# Schematic_L1.net
KiCad netlist of a schematic drawn in Altium Designer
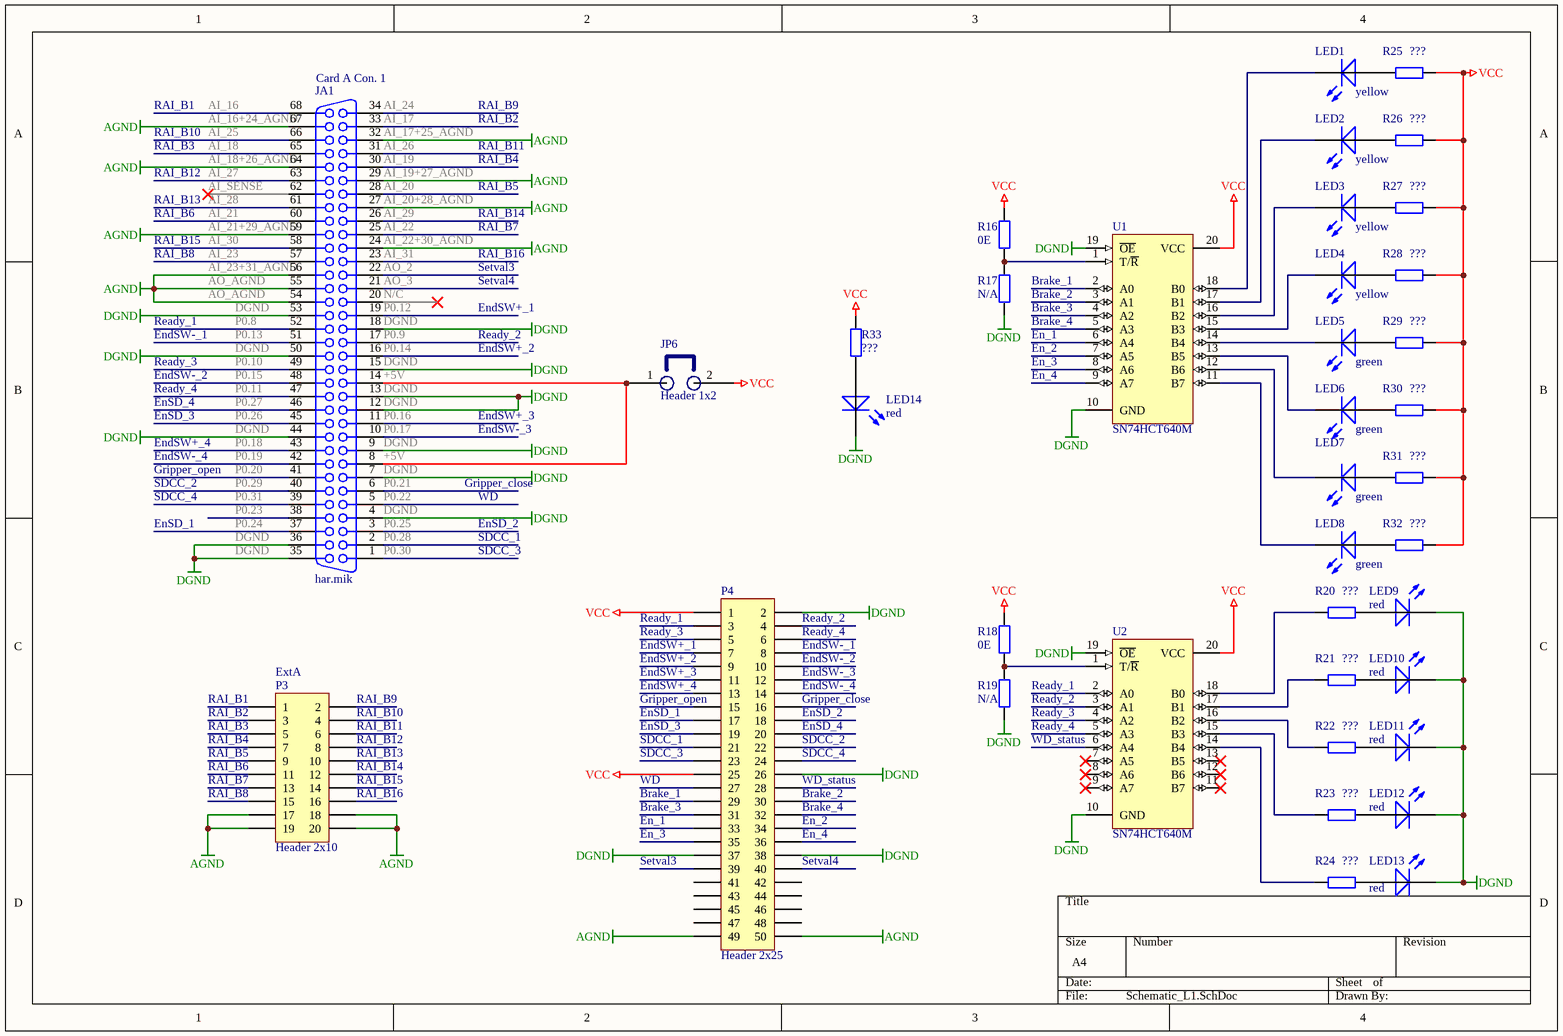
[diagram p0: Schematic_L1.SchDoc]

(export (version "E")
  (design (tool "Eeschema 10.0.6"))
  (components
    (comp (ref "JA1")
      (value "har.mik")
      (footprint "HAR-MIK P/S 68 SA")
      (description "TB 60 01 068 5232")
      (fields (field (name "PUBLISHER") "Altium Limited"))
      (libsource (lib "Integrated_Library") (part "Connector 68"))
    )
    (comp (ref "JP6")
      (value "Header 1x2")
      (footprint "Header - 1x2 - V")
      (libsource (lib "Integrated_Library") (part "Jumper"))
    )
    (comp (ref "LED1")
      (value "yellow")
      (footprint "KM2520")
      (description "Typical LED")
      (libsource (lib "mzueger") (part "LED"))
    )
    (comp (ref "LED2")
      (value "yellow")
      (footprint "KM2520")
      (description "Typical LED")
      (libsource (lib "mzueger") (part "LED"))
    )
    (comp (ref "LED3")
      (value "yellow")
      (footprint "KM2520")
      (description "Typical LED")
      (libsource (lib "mzueger") (part "LED"))
    )
    (comp (ref "LED4")
      (value "yellow")
      (footprint "KM2520")
      (description "Typical LED")
      (libsource (lib "mzueger") (part "LED"))
    )
    (comp (ref "LED5")
      (value "green")
      (footprint "KM2520")
      (description "Typical LED")
      (libsource (lib "mzueger") (part "LED"))
    )
    (comp (ref "LED6")
      (value "green")
      (footprint "KM2520")
      (description "Typical LED")
      (libsource (lib "mzueger") (part "LED"))
    )
    (comp (ref "LED7")
      (value "green")
      (footprint "KM2520")
      (description "Typical LED")
      (libsource (lib "mzueger") (part "LED"))
    )
    (comp (ref "LED8")
      (value "green")
      (footprint "KM2520")
      (description "Typical LED")
      (libsource (lib "mzueger") (part "LED"))
    )
    (comp (ref "LED9")
      (value "red")
      (footprint "KM2520")
      (description "Typical LED")
      (libsource (lib "mzueger") (part "LED"))
    )
    (comp (ref "LED10")
      (value "red")
      (footprint "KM2520")
      (description "Typical LED")
      (libsource (lib "mzueger") (part "LED"))
    )
    (comp (ref "LED11")
      (value "red")
      (footprint "KM2520")
      (description "Typical LED")
      (libsource (lib "mzueger") (part "LED"))
    )
    (comp (ref "LED12")
      (value "red")
      (footprint "KM2520")
      (description "Typical LED")
      (libsource (lib "mzueger") (part "LED"))
    )
    (comp (ref "LED13")
      (value "red")
      (footprint "KM2520")
      (description "Typical LED")
      (libsource (lib "mzueger") (part "LED"))
    )
    (comp (ref "LED14")
      (value "red")
      (footprint "KM2520")
      (description "Typical LED")
      (libsource (lib "mzueger") (part "LED"))
    )
    (comp (ref "P3")
      (value "Header 2x10")
      (footprint "Header - 2x10 - V")
      (description "Header, 10-Pin, Dual row")
      (fields (field (name "PUBLISHER") "Altium Limited"))
      (libsource (lib "mzueger") (part "Header 2x10"))
    )
    (comp (ref "P4")
      (value "Header 2x25")
      (footprint "Header - 2x25 - V")
      (description "Header, 25-Pin, Dual row")
      (fields (field (name "PUBLISHER") "Altium Limited"))
      (libsource (lib "mzueger") (part "Header 2x25"))
    )
    (comp (ref "R16")
      (value "0E")
      (footprint "0805")
      (description "Resistor")
      (fields (field (name "#PUBLISHER") "Dr. A. Heinzelmann"))
      (libsource (lib "") (part "R_1"))
    )
    (comp (ref "R17")
      (value "N/A")
      (footprint "0805")
      (description "Resistor")
      (fields (field (name "#PUBLISHER") "Dr. A. Heinzelmann"))
      (libsource (lib "") (part "R_1"))
    )
    (comp (ref "R18")
      (value "0E")
      (footprint "0805")
      (description "Resistor")
      (fields (field (name "#PUBLISHER") "Dr. A. Heinzelmann"))
      (libsource (lib "") (part "R_1"))
    )
    (comp (ref "R19")
      (value "N/A")
      (footprint "0805")
      (description "Resistor")
      (fields (field (name "#PUBLISHER") "Dr. A. Heinzelmann"))
      (libsource (lib "") (part "R_1"))
    )
    (comp (ref "R20")
      (value "???")
      (footprint "0805")
      (description "Resistor")
      (fields (field (name "#PUBLISHER") "Dr. A. Heinzelmann"))
      (libsource (lib "mzueger") (part "R"))
    )
    (comp (ref "R21")
      (value "???")
      (footprint "0805")
      (description "Resistor")
      (fields (field (name "#PUBLISHER") "Dr. A. Heinzelmann"))
      (libsource (lib "mzueger") (part "R"))
    )
    (comp (ref "R22")
      (value "???")
      (footprint "0805")
      (description "Resistor")
      (fields (field (name "#PUBLISHER") "Dr. A. Heinzelmann"))
      (libsource (lib "mzueger") (part "R"))
    )
    (comp (ref "R23")
      (value "???")
      (footprint "0805")
      (description "Resistor")
      (fields (field (name "#PUBLISHER") "Dr. A. Heinzelmann"))
      (libsource (lib "mzueger") (part "R"))
    )
    (comp (ref "R24")
      (value "???")
      (footprint "0805")
      (description "Resistor")
      (fields (field (name "#PUBLISHER") "Dr. A. Heinzelmann"))
      (libsource (lib "mzueger") (part "R"))
    )
    (comp (ref "R25")
      (value "???")
      (footprint "0805")
      (description "Resistor")
      (fields (field (name "#PUBLISHER") "Dr. A. Heinzelmann"))
      (libsource (lib "mzueger") (part "R"))
    )
    (comp (ref "R26")
      (value "???")
      (footprint "0805")
      (description "Resistor")
      (fields (field (name "#PUBLISHER") "Dr. A. Heinzelmann"))
      (libsource (lib "mzueger") (part "R"))
    )
    (comp (ref "R27")
      (value "???")
      (footprint "0805")
      (description "Resistor")
      (fields (field (name "#PUBLISHER") "Dr. A. Heinzelmann"))
      (libsource (lib "mzueger") (part "R"))
    )
    (comp (ref "R28")
      (value "???")
      (footprint "0805")
      (description "Resistor")
      (fields (field (name "#PUBLISHER") "Dr. A. Heinzelmann"))
      (libsource (lib "mzueger") (part "R"))
    )
    (comp (ref "R29")
      (value "???")
      (footprint "0805")
      (description "Resistor")
      (fields (field (name "#PUBLISHER") "Dr. A. Heinzelmann"))
      (libsource (lib "mzueger") (part "R"))
    )
    (comp (ref "R30")
      (value "???")
      (footprint "0805")
      (description "Resistor")
      (fields (field (name "#PUBLISHER") "Dr. A. Heinzelmann"))
      (libsource (lib "mzueger") (part "R"))
    )
    (comp (ref "R31")
      (value "???")
      (footprint "0805")
      (description "Resistor")
      (fields (field (name "#PUBLISHER") "Dr. A. Heinzelmann"))
      (libsource (lib "mzueger") (part "R"))
    )
    (comp (ref "R32")
      (value "???")
      (footprint "0805")
      (description "Resistor")
      (fields (field (name "#PUBLISHER") "Dr. A. Heinzelmann"))
      (libsource (lib "mzueger") (part "R"))
    )
    (comp (ref "R33")
      (value "???")
      (footprint "0805")
      (description "Resistor")
      (fields (field (name "#PUBLISHER") "Dr. A. Heinzelmann"))
      (libsource (lib "") (part "R_1"))
    )
    (comp (ref "U1")
      (value "SN74HCT640M")
      (footprint "DW020_N")
      (description "Octal Bus Transceiver with 3-State Outputs")
      (fields (field (name "PUBLISHER") "Altium Limited"))
      (libsource (lib "TI Interface 8-Bit Line Transceiver") (part "SN74HCT640DW"))
    )
    (comp (ref "U2")
      (value "SN74HCT640M")
      (footprint "DW020_N")
      (description "Octal Bus Transceiver with 3-State Outputs")
      (fields (field (name "PUBLISHER") "Altium Limited"))
      (libsource (lib "TI Interface 8-Bit Line Transceiver") (part "SN74HCT640DW"))
    )
  )
  (nets
    (net (code "1") (name "/Brake_1") (class "Default")
      (node (ref "P4") (pin "29") (pinfunction "29_29") (pintype "passive"))
      (node (ref "U1") (pin "2") (pinfunction "A0_2") (pintype "bidirectional"))
    )
    (net (code "2") (name "/Brake_2") (class "Default")
      (node (ref "P4") (pin "30") (pinfunction "30_30") (pintype "passive"))
      (node (ref "U1") (pin "3") (pinfunction "A1_3") (pintype "bidirectional"))
    )
    (net (code "3") (name "/Brake_3") (class "Default")
      (node (ref "P4") (pin "31") (pinfunction "31_31") (pintype "passive"))
      (node (ref "U1") (pin "4") (pinfunction "A2_4") (pintype "bidirectional"))
    )
    (net (code "4") (name "/Brake_4") (class "Default")
      (node (ref "P4") (pin "32") (pinfunction "32_32") (pintype "passive"))
      (node (ref "U1") (pin "5") (pinfunction "A3_5") (pintype "bidirectional"))
    )
    (net (code "5") (name "/EnSD_1") (class "Default")
      (node (ref "JA1") (pin "37") (pinfunction "37_37") (pintype "passive"))
      (node (ref "P4") (pin "17") (pinfunction "17_17") (pintype "passive"))
    )
    (net (code "6") (name "/EnSD_2") (class "Default")
      (node (ref "JA1") (pin "3") (pinfunction "3_3") (pintype "passive"))
      (node (ref "P4") (pin "18") (pinfunction "18_18") (pintype "passive"))
    )
    (net (code "7") (name "/EnSD_3") (class "Default")
      (node (ref "JA1") (pin "45") (pinfunction "45_45") (pintype "passive"))
      (node (ref "P4") (pin "19") (pinfunction "19_19") (pintype "passive"))
    )
    (net (code "8") (name "/EnSD_4") (class "Default")
      (node (ref "JA1") (pin "46") (pinfunction "46_46") (pintype "passive"))
      (node (ref "P4") (pin "20") (pinfunction "20_20") (pintype "passive"))
    )
    (net (code "9") (name "/En_1") (class "Default")
      (node (ref "P4") (pin "33") (pinfunction "33_33") (pintype "passive"))
      (node (ref "U1") (pin "6") (pinfunction "A4_6") (pintype "bidirectional"))
    )
    (net (code "10") (name "/En_2") (class "Default")
      (node (ref "P4") (pin "34") (pinfunction "34_34") (pintype "passive"))
      (node (ref "U1") (pin "7") (pinfunction "A5_7") (pintype "bidirectional"))
    )
    (net (code "11") (name "/En_3") (class "Default")
      (node (ref "P4") (pin "35") (pinfunction "35_35") (pintype "passive"))
      (node (ref "U1") (pin "8") (pinfunction "A6_8") (pintype "bidirectional"))
    )
    (net (code "12") (name "/En_4") (class "Default")
      (node (ref "P4") (pin "36") (pinfunction "36_36") (pintype "passive"))
      (node (ref "U1") (pin "9") (pinfunction "A7_9") (pintype "bidirectional"))
    )
    (net (code "13") (name "/EndSW+_1") (class "Default")
      (node (ref "JA1") (pin "19") (pinfunction "19_19") (pintype "passive"))
      (node (ref "P4") (pin "7") (pinfunction "7_7") (pintype "passive"))
    )
    (net (code "14") (name "/EndSW+_2") (class "Default")
      (node (ref "JA1") (pin "16") (pinfunction "16_16") (pintype "passive"))
      (node (ref "P4") (pin "9") (pinfunction "9_9") (pintype "passive"))
    )
    (net (code "15") (name "/EndSW+_3") (class "Default")
      (node (ref "JA1") (pin "11") (pinfunction "11_11") (pintype "passive"))
      (node (ref "P4") (pin "11") (pinfunction "11_11") (pintype "passive"))
    )
    (net (code "16") (name "/EndSW+_4") (class "Default")
      (node (ref "JA1") (pin "43") (pinfunction "43_43") (pintype "passive"))
      (node (ref "P4") (pin "13") (pinfunction "13_13") (pintype "passive"))
    )
    (net (code "17") (name "/EndSW-_1") (class "Default")
      (node (ref "JA1") (pin "51") (pinfunction "51_51") (pintype "passive"))
      (node (ref "P4") (pin "8") (pinfunction "8_8") (pintype "passive"))
    )
    (net (code "18") (name "/EndSW-_2") (class "Default")
      (node (ref "JA1") (pin "48") (pinfunction "48_48") (pintype "passive"))
      (node (ref "P4") (pin "10") (pinfunction "10_10") (pintype "passive"))
    )
    (net (code "19") (name "/EndSW-_3") (class "Default")
      (node (ref "JA1") (pin "10") (pinfunction "10_10") (pintype "passive"))
      (node (ref "P4") (pin "12") (pinfunction "12_12") (pintype "passive"))
    )
    (net (code "20") (name "/EndSW-_4") (class "Default")
      (node (ref "JA1") (pin "42") (pinfunction "42_42") (pintype "passive"))
      (node (ref "P4") (pin "14") (pinfunction "14_14") (pintype "passive"))
    )
    (net (code "21") (name "/Gripper_close") (class "Default")
      (node (ref "JA1") (pin "6") (pinfunction "6_6") (pintype "passive"))
      (node (ref "P4") (pin "16") (pinfunction "16_16") (pintype "passive"))
    )
    (net (code "22") (name "/Gripper_open") (class "Default")
      (node (ref "JA1") (pin "41") (pinfunction "41_41") (pintype "passive"))
      (node (ref "P4") (pin "15") (pinfunction "15_15") (pintype "passive"))
    )
    (net (code "23") (name "/RAI_B1") (class "Default")
      (node (ref "JA1") (pin "68") (pinfunction "68_68") (pintype "passive"))
      (node (ref "P3") (pin "1") (pinfunction "1_1") (pintype "passive"))
    )
    (net (code "24") (name "/RAI_B2") (class "Default")
      (node (ref "JA1") (pin "33") (pinfunction "33_33") (pintype "passive"))
      (node (ref "P3") (pin "3") (pinfunction "3_3") (pintype "passive"))
    )
    (net (code "25") (name "/RAI_B3") (class "Default")
      (node (ref "JA1") (pin "65") (pinfunction "65_65") (pintype "passive"))
      (node (ref "P3") (pin "5") (pinfunction "5_5") (pintype "passive"))
    )
    (net (code "26") (name "/RAI_B4") (class "Default")
      (node (ref "JA1") (pin "30") (pinfunction "30_30") (pintype "passive"))
      (node (ref "P3") (pin "7") (pinfunction "7_7") (pintype "passive"))
    )
    (net (code "27") (name "/RAI_B5") (class "Default")
      (node (ref "JA1") (pin "28") (pinfunction "28_28") (pintype "passive"))
      (node (ref "P3") (pin "9") (pinfunction "9_9") (pintype "passive"))
    )
    (net (code "28") (name "/RAI_B6") (class "Default")
      (node (ref "JA1") (pin "60") (pinfunction "60_60") (pintype "passive"))
      (node (ref "P3") (pin "11") (pinfunction "11_11") (pintype "passive"))
    )
    (net (code "29") (name "/RAI_B7") (class "Default")
      (node (ref "JA1") (pin "25") (pinfunction "25_25") (pintype "passive"))
      (node (ref "P3") (pin "13") (pinfunction "13_13") (pintype "passive"))
    )
    (net (code "30") (name "/RAI_B8") (class "Default")
      (node (ref "JA1") (pin "57") (pinfunction "57_57") (pintype "passive"))
      (node (ref "P3") (pin "15") (pinfunction "15_15") (pintype "passive"))
    )
    (net (code "31") (name "/RAI_B9") (class "Default")
      (node (ref "JA1") (pin "34") (pinfunction "34_34") (pintype "passive"))
      (node (ref "P3") (pin "2") (pinfunction "2_2") (pintype "passive"))
    )
    (net (code "32") (name "/RAI_B10") (class "Default")
      (node (ref "JA1") (pin "66") (pinfunction "66_66") (pintype "passive"))
      (node (ref "P3") (pin "4") (pinfunction "4_4") (pintype "passive"))
    )
    (net (code "33") (name "/RAI_B11") (class "Default")
      (node (ref "JA1") (pin "31") (pinfunction "31_31") (pintype "passive"))
      (node (ref "P3") (pin "6") (pinfunction "6_6") (pintype "passive"))
    )
    (net (code "34") (name "/RAI_B12") (class "Default")
      (node (ref "JA1") (pin "63") (pinfunction "63_63") (pintype "passive"))
      (node (ref "P3") (pin "8") (pinfunction "8_8") (pintype "passive"))
    )
    (net (code "35") (name "/RAI_B13") (class "Default")
      (node (ref "JA1") (pin "61") (pinfunction "61_61") (pintype "passive"))
      (node (ref "P3") (pin "10") (pinfunction "10_10") (pintype "passive"))
    )
    (net (code "36") (name "/RAI_B14") (class "Default")
      (node (ref "JA1") (pin "26") (pinfunction "26_26") (pintype "passive"))
      (node (ref "P3") (pin "12") (pinfunction "12_12") (pintype "passive"))
    )
    (net (code "37") (name "/RAI_B15") (class "Default")
      (node (ref "JA1") (pin "58") (pinfunction "58_58") (pintype "passive"))
      (node (ref "P3") (pin "14") (pinfunction "14_14") (pintype "passive"))
    )
    (net (code "38") (name "/RAI_B16") (class "Default")
      (node (ref "JA1") (pin "23") (pinfunction "23_23") (pintype "passive"))
      (node (ref "P3") (pin "16") (pinfunction "16_16") (pintype "passive"))
    )
    (net (code "39") (name "/Ready_1") (class "Default")
      (node (ref "JA1") (pin "52") (pinfunction "52_52") (pintype "passive"))
      (node (ref "P4") (pin "3") (pinfunction "3_3") (pintype "passive"))
      (node (ref "U2") (pin "2") (pinfunction "A0_2") (pintype "bidirectional"))
    )
    (net (code "40") (name "/Ready_2") (class "Default")
      (node (ref "JA1") (pin "17") (pinfunction "17_17") (pintype "passive"))
      (node (ref "P4") (pin "4") (pinfunction "4_4") (pintype "passive"))
      (node (ref "U2") (pin "3") (pinfunction "A1_3") (pintype "bidirectional"))
    )
    (net (code "41") (name "/Ready_3") (class "Default")
      (node (ref "JA1") (pin "49") (pinfunction "49_49") (pintype "passive"))
      (node (ref "P4") (pin "5") (pinfunction "5_5") (pintype "passive"))
      (node (ref "U2") (pin "4") (pinfunction "A2_4") (pintype "bidirectional"))
    )
    (net (code "42") (name "/Ready_4") (class "Default")
      (node (ref "JA1") (pin "47") (pinfunction "47_47") (pintype "passive"))
      (node (ref "P4") (pin "6") (pinfunction "6_6") (pintype "passive"))
      (node (ref "U2") (pin "5") (pinfunction "A3_5") (pintype "bidirectional"))
    )
    (net (code "43") (name "/SDCC_1") (class "Default")
      (node (ref "JA1") (pin "2") (pinfunction "2_2") (pintype "passive"))
      (node (ref "P4") (pin "21") (pinfunction "21_21") (pintype "passive"))
    )
    (net (code "44") (name "/SDCC_2") (class "Default")
      (node (ref "JA1") (pin "40") (pinfunction "40_40") (pintype "passive"))
      (node (ref "P4") (pin "22") (pinfunction "22_22") (pintype "passive"))
    )
    (net (code "45") (name "/SDCC_3") (class "Default")
      (node (ref "JA1") (pin "1") (pinfunction "1_1") (pintype "passive"))
      (node (ref "P4") (pin "23") (pinfunction "23_23") (pintype "passive"))
    )
    (net (code "46") (name "/SDCC_4") (class "Default")
      (node (ref "JA1") (pin "39") (pinfunction "39_39") (pintype "passive"))
      (node (ref "P4") (pin "24") (pinfunction "24_24") (pintype "passive"))
    )
    (net (code "47") (name "/Setval3") (class "Default")
      (node (ref "JA1") (pin "22") (pinfunction "22_22") (pintype "passive"))
      (node (ref "P4") (pin "39") (pinfunction "39_39") (pintype "passive"))
    )
    (net (code "48") (name "/Setval4") (class "Default")
      (node (ref "JA1") (pin "21") (pinfunction "21_21") (pintype "passive"))
      (node (ref "P4") (pin "40") (pinfunction "40_40") (pintype "passive"))
    )
    (net (code "49") (name "/WD") (class "Default")
      (node (ref "JA1") (pin "5") (pinfunction "5_5") (pintype "passive"))
      (node (ref "P4") (pin "27") (pinfunction "27_27") (pintype "passive"))
    )
    (net (code "50") (name "/WD_status") (class "Default")
      (node (ref "P4") (pin "28") (pinfunction "28_28") (pintype "passive"))
      (node (ref "U2") (pin "6") (pinfunction "A4_6") (pintype "bidirectional"))
    )
    (net (code "51") (name "AGND") (class "Default")
      (node (ref "JA1") (pin "24") (pinfunction "24_24") (pintype "passive"))
      (node (ref "JA1") (pin "27") (pinfunction "27_27") (pintype "passive"))
      (node (ref "JA1") (pin "29") (pinfunction "29_29") (pintype "passive"))
      (node (ref "JA1") (pin "32") (pinfunction "32_32") (pintype "passive"))
      (node (ref "JA1") (pin "54") (pinfunction "54_54") (pintype "passive"))
      (node (ref "JA1") (pin "55") (pinfunction "55_55") (pintype "passive"))
      (node (ref "JA1") (pin "56") (pinfunction "56_56") (pintype "passive"))
      (node (ref "JA1") (pin "59") (pinfunction "59_59") (pintype "passive"))
      (node (ref "JA1") (pin "64") (pinfunction "64_64") (pintype "passive"))
      (node (ref "JA1") (pin "67") (pinfunction "67_67") (pintype "passive"))
      (node (ref "P3") (pin "17") (pinfunction "17_17") (pintype "passive"))
      (node (ref "P3") (pin "18") (pinfunction "18_18") (pintype "passive"))
      (node (ref "P3") (pin "19") (pinfunction "19_19") (pintype "passive"))
      (node (ref "P3") (pin "20") (pinfunction "20_20") (pintype "passive"))
      (node (ref "P4") (pin "49") (pinfunction "49_49") (pintype "passive"))
      (node (ref "P4") (pin "50") (pinfunction "50_50") (pintype "passive"))
    )
    (net (code "52") (name "DGND") (class "Default")
      (node (ref "JA1") (pin "12") (pinfunction "12_12") (pintype "passive"))
      (node (ref "JA1") (pin "13") (pinfunction "13_13") (pintype "passive"))
      (node (ref "JA1") (pin "15") (pinfunction "15_15") (pintype "passive"))
      (node (ref "JA1") (pin "18") (pinfunction "18_18") (pintype "passive"))
      (node (ref "JA1") (pin "35") (pinfunction "35_35") (pintype "passive"))
      (node (ref "JA1") (pin "36") (pinfunction "36_36") (pintype "passive"))
      (node (ref "JA1") (pin "4") (pinfunction "4_4") (pintype "passive"))
      (node (ref "JA1") (pin "44") (pinfunction "44_44") (pintype "passive"))
      (node (ref "JA1") (pin "50") (pinfunction "50_50") (pintype "passive"))
      (node (ref "JA1") (pin "53") (pinfunction "53_53") (pintype "passive"))
      (node (ref "JA1") (pin "7") (pinfunction "7_7") (pintype "passive"))
      (node (ref "JA1") (pin "9") (pinfunction "9_9") (pintype "passive"))
      (node (ref "LED10") (pin "1") (pinfunction "K_1") (pintype "passive"))
      (node (ref "LED11") (pin "1") (pinfunction "K_1") (pintype "passive"))
      (node (ref "LED12") (pin "1") (pinfunction "K_1") (pintype "passive"))
      (node (ref "LED13") (pin "1") (pinfunction "K_1") (pintype "passive"))
      (node (ref "LED14") (pin "1") (pinfunction "K_1") (pintype "passive"))
      (node (ref "LED9") (pin "1") (pinfunction "K_1") (pintype "passive"))
      (node (ref "P4") (pin "2") (pinfunction "2_2") (pintype "passive"))
      (node (ref "P4") (pin "26") (pinfunction "26_26") (pintype "passive"))
      (node (ref "P4") (pin "37") (pinfunction "37_37") (pintype "passive"))
      (node (ref "P4") (pin "38") (pinfunction "38_38") (pintype "passive"))
      (node (ref "R17") (pin "1") (pinfunction "1_1") (pintype "passive"))
      (node (ref "R19") (pin "1") (pinfunction "1_1") (pintype "passive"))
      (node (ref "U1") (pin "10") (pinfunction "GND_10") (pintype "power_in"))
      (node (ref "U1") (pin "19") (pinfunction "~{OE}_19") (pintype "input"))
      (node (ref "U2") (pin "10") (pinfunction "GND_10") (pintype "power_in"))
      (node (ref "U2") (pin "19") (pinfunction "~{OE}_19") (pintype "input"))
    )
    (net (code "53") (name "Net-(JA1-Pad14)") (class "Default")
      (node (ref "JA1") (pin "14") (pinfunction "14_14") (pintype "passive"))
      (node (ref "JA1") (pin "8") (pinfunction "8_8") (pintype "passive"))
      (node (ref "JP6") (pin "1") (pinfunction "1_1") (pintype "passive"))
    )
    (net (code "54") (name "Net-(LED1-A)") (class "Default")
      (node (ref "LED1") (pin "2") (pinfunction "A_2") (pintype "passive"))
      (node (ref "R25") (pin "1") (pinfunction "1_1") (pintype "passive"))
    )
    (net (code "55") (name "Net-(LED1-K)") (class "Default")
      (node (ref "LED1") (pin "1") (pinfunction "K_1") (pintype "passive"))
      (node (ref "U1") (pin "18") (pinfunction "B0_18") (pintype "bidirectional"))
    )
    (net (code "56") (name "Net-(LED2-A)") (class "Default")
      (node (ref "LED2") (pin "2") (pinfunction "A_2") (pintype "passive"))
      (node (ref "R26") (pin "1") (pinfunction "1_1") (pintype "passive"))
    )
    (net (code "57") (name "Net-(LED2-K)") (class "Default")
      (node (ref "LED2") (pin "1") (pinfunction "K_1") (pintype "passive"))
      (node (ref "U1") (pin "17") (pinfunction "B1_17") (pintype "bidirectional"))
    )
    (net (code "58") (name "Net-(LED3-A)") (class "Default")
      (node (ref "LED3") (pin "2") (pinfunction "A_2") (pintype "passive"))
      (node (ref "R27") (pin "1") (pinfunction "1_1") (pintype "passive"))
    )
    (net (code "59") (name "Net-(LED3-K)") (class "Default")
      (node (ref "LED3") (pin "1") (pinfunction "K_1") (pintype "passive"))
      (node (ref "U1") (pin "16") (pinfunction "B2_16") (pintype "bidirectional"))
    )
    (net (code "60") (name "Net-(LED4-A)") (class "Default")
      (node (ref "LED4") (pin "2") (pinfunction "A_2") (pintype "passive"))
      (node (ref "R28") (pin "1") (pinfunction "1_1") (pintype "passive"))
    )
    (net (code "61") (name "Net-(LED4-K)") (class "Default")
      (node (ref "LED4") (pin "1") (pinfunction "K_1") (pintype "passive"))
      (node (ref "U1") (pin "15") (pinfunction "B3_15") (pintype "bidirectional"))
    )
    (net (code "62") (name "Net-(LED5-A)") (class "Default")
      (node (ref "LED5") (pin "2") (pinfunction "A_2") (pintype "passive"))
      (node (ref "R29") (pin "1") (pinfunction "1_1") (pintype "passive"))
    )
    (net (code "63") (name "Net-(LED5-K)") (class "Default")
      (node (ref "LED5") (pin "1") (pinfunction "K_1") (pintype "passive"))
      (node (ref "U1") (pin "14") (pinfunction "B4_14") (pintype "bidirectional"))
    )
    (net (code "64") (name "Net-(LED6-A)") (class "Default")
      (node (ref "LED6") (pin "2") (pinfunction "A_2") (pintype "passive"))
      (node (ref "R30") (pin "1") (pinfunction "1_1") (pintype "passive"))
    )
    (net (code "65") (name "Net-(LED6-K)") (class "Default")
      (node (ref "LED6") (pin "1") (pinfunction "K_1") (pintype "passive"))
      (node (ref "U1") (pin "13") (pinfunction "B5_13") (pintype "bidirectional"))
    )
    (net (code "66") (name "Net-(LED7-A)") (class "Default")
      (node (ref "LED7") (pin "2") (pinfunction "A_2") (pintype "passive"))
      (node (ref "R31") (pin "1") (pinfunction "1_1") (pintype "passive"))
    )
    (net (code "67") (name "Net-(LED7-K)") (class "Default")
      (node (ref "LED7") (pin "1") (pinfunction "K_1") (pintype "passive"))
      (node (ref "U1") (pin "12") (pinfunction "B6_12") (pintype "bidirectional"))
    )
    (net (code "68") (name "Net-(LED8-A)") (class "Default")
      (node (ref "LED8") (pin "2") (pinfunction "A_2") (pintype "passive"))
      (node (ref "R32") (pin "1") (pinfunction "1_1") (pintype "passive"))
    )
    (net (code "69") (name "Net-(LED8-K)") (class "Default")
      (node (ref "LED8") (pin "1") (pinfunction "K_1") (pintype "passive"))
      (node (ref "U1") (pin "11") (pinfunction "B7_11") (pintype "bidirectional"))
    )
    (net (code "70") (name "Net-(LED9-A)") (class "Default")
      (node (ref "LED9") (pin "2") (pinfunction "A_2") (pintype "passive"))
      (node (ref "R20") (pin "2") (pinfunction "2_2") (pintype "passive"))
    )
    (net (code "71") (name "Net-(LED10-A)") (class "Default")
      (node (ref "LED10") (pin "2") (pinfunction "A_2") (pintype "passive"))
      (node (ref "R21") (pin "2") (pinfunction "2_2") (pintype "passive"))
    )
    (net (code "72") (name "Net-(LED11-A)") (class "Default")
      (node (ref "LED11") (pin "2") (pinfunction "A_2") (pintype "passive"))
      (node (ref "R22") (pin "2") (pinfunction "2_2") (pintype "passive"))
    )
    (net (code "73") (name "Net-(LED12-A)") (class "Default")
      (node (ref "LED12") (pin "2") (pinfunction "A_2") (pintype "passive"))
      (node (ref "R23") (pin "2") (pinfunction "2_2") (pintype "passive"))
    )
    (net (code "74") (name "Net-(LED13-A)") (class "Default")
      (node (ref "LED13") (pin "2") (pinfunction "A_2") (pintype "passive"))
      (node (ref "R24") (pin "2") (pinfunction "2_2") (pintype "passive"))
    )
    (net (code "75") (name "Net-(LED14-A)") (class "Default")
      (node (ref "LED14") (pin "2") (pinfunction "A_2") (pintype "passive"))
      (node (ref "R33") (pin "1") (pinfunction "1_1") (pintype "passive"))
    )
    (net (code "76") (name "Net-(U1-T{slash}~{R})") (class "Default")
      (node (ref "R16") (pin "1") (pinfunction "1_1") (pintype "passive"))
      (node (ref "R17") (pin "2") (pinfunction "2_2") (pintype "passive"))
      (node (ref "U1") (pin "1") (pinfunction "T/~{R}_1") (pintype "input"))
    )
    (net (code "77") (name "Net-(U2-B0)") (class "Default")
      (node (ref "R20") (pin "1") (pinfunction "1_1") (pintype "passive"))
      (node (ref "U2") (pin "18") (pinfunction "B0_18") (pintype "bidirectional"))
    )
    (net (code "78") (name "Net-(U2-B1)") (class "Default")
      (node (ref "R21") (pin "1") (pinfunction "1_1") (pintype "passive"))
      (node (ref "U2") (pin "17") (pinfunction "B1_17") (pintype "bidirectional"))
    )
    (net (code "79") (name "Net-(U2-B2)") (class "Default")
      (node (ref "R22") (pin "1") (pinfunction "1_1") (pintype "passive"))
      (node (ref "U2") (pin "16") (pinfunction "B2_16") (pintype "bidirectional"))
    )
    (net (code "80") (name "Net-(U2-B3)") (class "Default")
      (node (ref "R23") (pin "1") (pinfunction "1_1") (pintype "passive"))
      (node (ref "U2") (pin "15") (pinfunction "B3_15") (pintype "bidirectional"))
    )
    (net (code "81") (name "Net-(U2-B4)") (class "Default")
      (node (ref "R24") (pin "1") (pinfunction "1_1") (pintype "passive"))
      (node (ref "U2") (pin "14") (pinfunction "B4_14") (pintype "bidirectional"))
    )
    (net (code "82") (name "Net-(U2-T{slash}~{R})") (class "Default")
      (node (ref "R18") (pin "1") (pinfunction "1_1") (pintype "passive"))
      (node (ref "R19") (pin "2") (pinfunction "2_2") (pintype "passive"))
      (node (ref "U2") (pin "1") (pinfunction "T/~{R}_1") (pintype "input"))
    )
    (net (code "83") (name "VCC") (class "Default")
      (node (ref "JP6") (pin "2") (pinfunction "2_2") (pintype "passive"))
      (node (ref "P4") (pin "1") (pinfunction "1_1") (pintype "passive"))
      (node (ref "P4") (pin "25") (pinfunction "25_25") (pintype "passive"))
      (node (ref "R16") (pin "2") (pinfunction "2_2") (pintype "passive"))
      (node (ref "R18") (pin "2") (pinfunction "2_2") (pintype "passive"))
      (node (ref "R25") (pin "2") (pinfunction "2_2") (pintype "passive"))
      (node (ref "R26") (pin "2") (pinfunction "2_2") (pintype "passive"))
      (node (ref "R27") (pin "2") (pinfunction "2_2") (pintype "passive"))
      (node (ref "R28") (pin "2") (pinfunction "2_2") (pintype "passive"))
      (node (ref "R29") (pin "2") (pinfunction "2_2") (pintype "passive"))
      (node (ref "R30") (pin "2") (pinfunction "2_2") (pintype "passive"))
      (node (ref "R31") (pin "2") (pinfunction "2_2") (pintype "passive"))
      (node (ref "R32") (pin "2") (pinfunction "2_2") (pintype "passive"))
      (node (ref "R33") (pin "2") (pinfunction "2_2") (pintype "passive"))
      (node (ref "U1") (pin "20") (pinfunction "VCC_20") (pintype "power_in"))
      (node (ref "U2") (pin "20") (pinfunction "VCC_20") (pintype "power_in"))
    )
    (net (code "84") (name "unconnected-(JA1-Pad20)") (class "Default")
      (node (ref "JA1") (pin "20") (pinfunction "20_20") (pintype "passive+no_connect"))
    )
    (net (code "85") (name "unconnected-(JA1-Pad38)") (class "Default")
      (node (ref "JA1") (pin "38") (pinfunction "38_38") (pintype "passive"))
    )
    (net (code "86") (name "unconnected-(JA1-Pad62)") (class "Default")
      (node (ref "JA1") (pin "62") (pinfunction "62_62") (pintype "passive+no_connect"))
    )
    (net (code "87") (name "unconnected-(P4-Pad41)") (class "Default")
      (node (ref "P4") (pin "41") (pinfunction "41_41") (pintype "passive"))
    )
    (net (code "88") (name "unconnected-(P4-Pad42)") (class "Default")
      (node (ref "P4") (pin "42") (pinfunction "42_42") (pintype "passive"))
    )
    (net (code "89") (name "unconnected-(P4-Pad43)") (class "Default")
      (node (ref "P4") (pin "43") (pinfunction "43_43") (pintype "passive"))
    )
    (net (code "90") (name "unconnected-(P4-Pad44)") (class "Default")
      (node (ref "P4") (pin "44") (pinfunction "44_44") (pintype "passive"))
    )
    (net (code "91") (name "unconnected-(P4-Pad45)") (class "Default")
      (node (ref "P4") (pin "45") (pinfunction "45_45") (pintype "passive"))
    )
    (net (code "92") (name "unconnected-(P4-Pad46)") (class "Default")
      (node (ref "P4") (pin "46") (pinfunction "46_46") (pintype "passive"))
    )
    (net (code "93") (name "unconnected-(P4-Pad47)") (class "Default")
      (node (ref "P4") (pin "47") (pinfunction "47_47") (pintype "passive"))
    )
    (net (code "94") (name "unconnected-(P4-Pad48)") (class "Default")
      (node (ref "P4") (pin "48") (pinfunction "48_48") (pintype "passive"))
    )
    (net (code "95") (name "unconnected-(U2-A5-Pad7)") (class "Default")
      (node (ref "U2") (pin "7") (pinfunction "A5_7") (pintype "bidirectional+no_connect"))
    )
    (net (code "96") (name "unconnected-(U2-A6-Pad8)") (class "Default")
      (node (ref "U2") (pin "8") (pinfunction "A6_8") (pintype "bidirectional+no_connect"))
    )
    (net (code "97") (name "unconnected-(U2-A7-Pad9)") (class "Default")
      (node (ref "U2") (pin "9") (pinfunction "A7_9") (pintype "bidirectional+no_connect"))
    )
    (net (code "98") (name "unconnected-(U2-B5-Pad13)") (class "Default")
      (node (ref "U2") (pin "13") (pinfunction "B5_13") (pintype "bidirectional+no_connect"))
    )
    (net (code "99") (name "unconnected-(U2-B6-Pad12)") (class "Default")
      (node (ref "U2") (pin "12") (pinfunction "B6_12") (pintype "bidirectional+no_connect"))
    )
    (net (code "100") (name "unconnected-(U2-B7-Pad11)") (class "Default")
      (node (ref "U2") (pin "11") (pinfunction "B7_11") (pintype "bidirectional+no_connect"))
    )
  )
)
